# Sensor_ExpandBoard_LED.net
KiCad netlist of a schematic drawn in Altium Designer
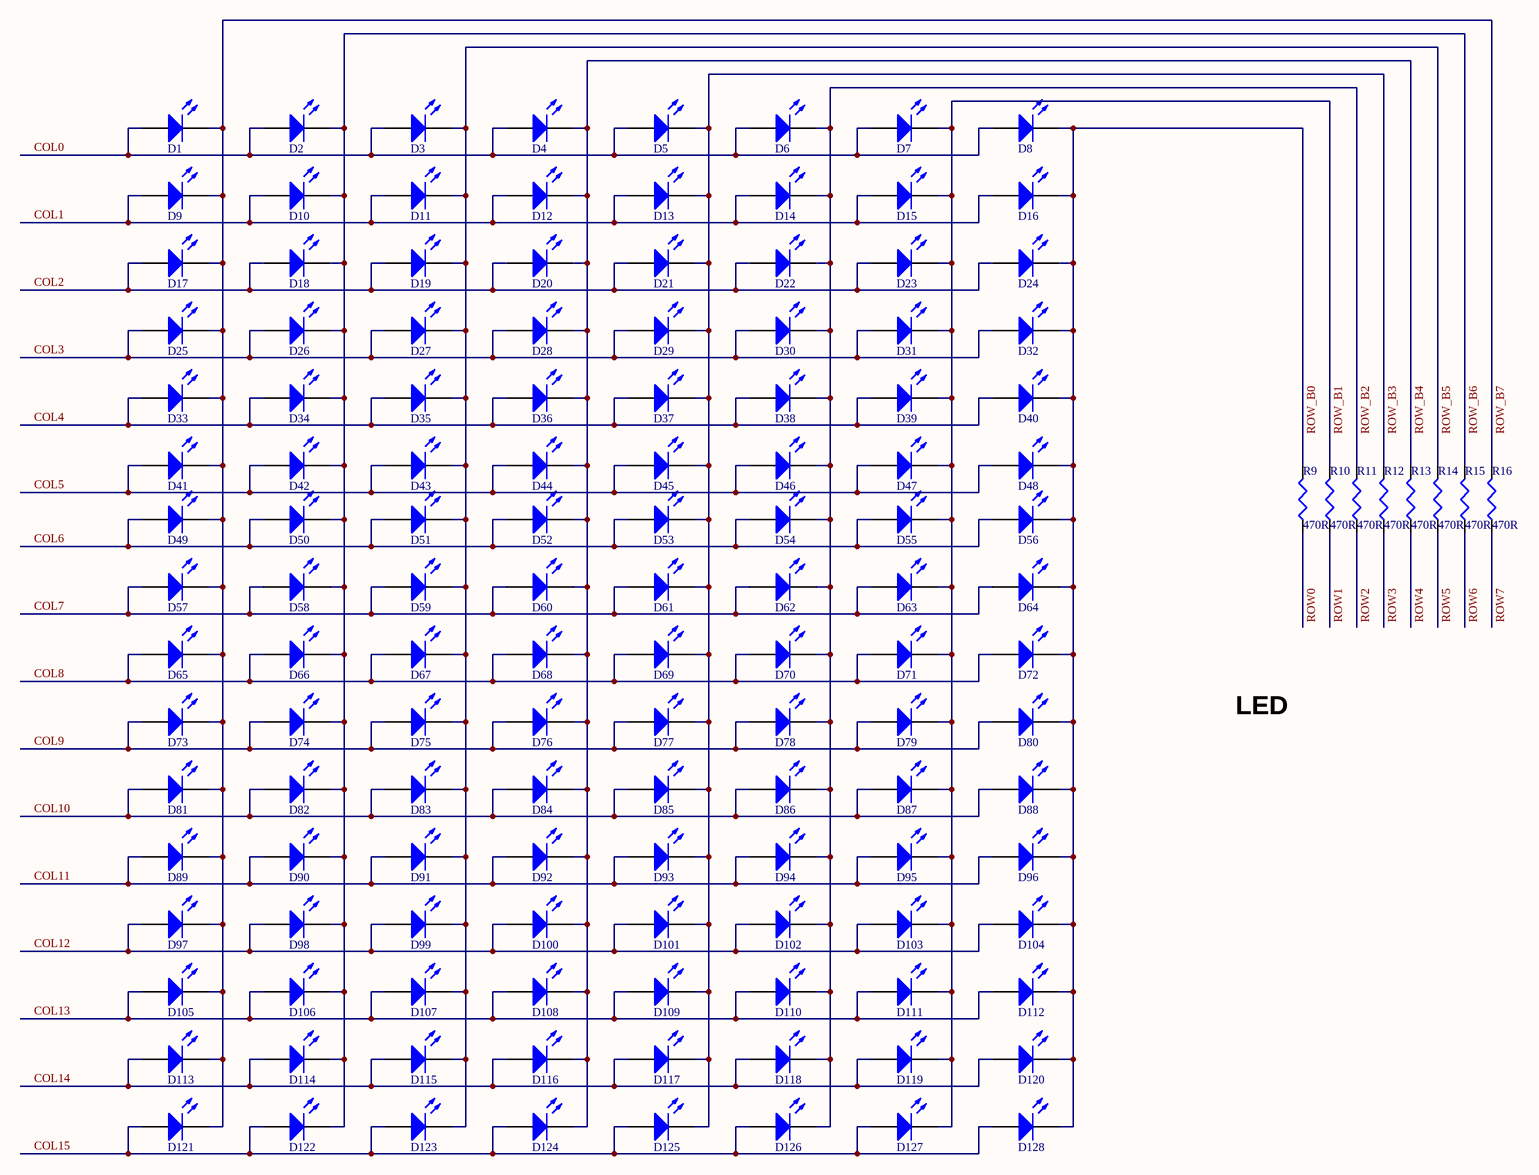
[diagram p0: Sensor_ExpandBoard_LED.SchDoc]

(export (version "E")
  (design (tool "Eeschema 10.0.6"))
  (components
    (comp (ref "D1")
      (value "Red")
      (footprint "LED_0603_SMALL")
      (description "发光二极管")
      (fields (field (name "PUBLISHER") "Altium Limited"))
      (libsource (lib "step") (part "LED"))
    )
    (comp (ref "D2")
      (value "Red")
      (footprint "LED_0603_SMALL")
      (description "发光二极管")
      (fields (field (name "PUBLISHER") "Altium Limited"))
      (libsource (lib "step") (part "LED"))
    )
    (comp (ref "D3")
      (value "Red")
      (footprint "LED_0603_SMALL")
      (description "发光二极管")
      (fields (field (name "PUBLISHER") "Altium Limited"))
      (libsource (lib "step") (part "LED"))
    )
    (comp (ref "D4")
      (value "Red")
      (footprint "LED_0603_SMALL")
      (description "发光二极管")
      (fields (field (name "PUBLISHER") "Altium Limited"))
      (libsource (lib "step") (part "LED"))
    )
    (comp (ref "D5")
      (value "Red")
      (footprint "LED_0603_SMALL")
      (description "发光二极管")
      (fields (field (name "PUBLISHER") "Altium Limited"))
      (libsource (lib "step") (part "LED"))
    )
    (comp (ref "D6")
      (value "Red")
      (footprint "LED_0603_SMALL")
      (description "发光二极管")
      (fields (field (name "PUBLISHER") "Altium Limited"))
      (libsource (lib "step") (part "LED"))
    )
    (comp (ref "D7")
      (value "Red")
      (footprint "LED_0603_SMALL")
      (description "发光二极管")
      (fields (field (name "PUBLISHER") "Altium Limited"))
      (libsource (lib "step") (part "LED"))
    )
    (comp (ref "D8")
      (value "Red")
      (footprint "LED_0603_SMALL")
      (description "发光二极管")
      (fields (field (name "PUBLISHER") "Altium Limited"))
      (libsource (lib "step") (part "LED"))
    )
    (comp (ref "D9")
      (value "Red")
      (footprint "LED_0603_SMALL")
      (description "发光二极管")
      (fields (field (name "PUBLISHER") "Altium Limited"))
      (libsource (lib "step") (part "LED"))
    )
    (comp (ref "D10")
      (value "Red")
      (footprint "LED_0603_SMALL")
      (description "发光二极管")
      (fields (field (name "PUBLISHER") "Altium Limited"))
      (libsource (lib "step") (part "LED"))
    )
    (comp (ref "D11")
      (value "Red")
      (footprint "LED_0603_SMALL")
      (description "发光二极管")
      (fields (field (name "PUBLISHER") "Altium Limited"))
      (libsource (lib "step") (part "LED"))
    )
    (comp (ref "D12")
      (value "Red")
      (footprint "LED_0603_SMALL")
      (description "发光二极管")
      (fields (field (name "PUBLISHER") "Altium Limited"))
      (libsource (lib "step") (part "LED"))
    )
    (comp (ref "D13")
      (value "Red")
      (footprint "LED_0603_SMALL")
      (description "发光二极管")
      (fields (field (name "PUBLISHER") "Altium Limited"))
      (libsource (lib "step") (part "LED"))
    )
    (comp (ref "D14")
      (value "Red")
      (footprint "LED_0603_SMALL")
      (description "发光二极管")
      (fields (field (name "PUBLISHER") "Altium Limited"))
      (libsource (lib "step") (part "LED"))
    )
    (comp (ref "D15")
      (value "Red")
      (footprint "LED_0603_SMALL")
      (description "发光二极管")
      (fields (field (name "PUBLISHER") "Altium Limited"))
      (libsource (lib "step") (part "LED"))
    )
    (comp (ref "D16")
      (value "Red")
      (footprint "LED_0603_SMALL")
      (description "发光二极管")
      (fields (field (name "PUBLISHER") "Altium Limited"))
      (libsource (lib "step") (part "LED"))
    )
    (comp (ref "D17")
      (value "Red")
      (footprint "LED_0603_SMALL")
      (description "发光二极管")
      (fields (field (name "PUBLISHER") "Altium Limited"))
      (libsource (lib "step") (part "LED"))
    )
    (comp (ref "D18")
      (value "Red")
      (footprint "LED_0603_SMALL")
      (description "发光二极管")
      (fields (field (name "PUBLISHER") "Altium Limited"))
      (libsource (lib "step") (part "LED"))
    )
    (comp (ref "D19")
      (value "Red")
      (footprint "LED_0603_SMALL")
      (description "发光二极管")
      (fields (field (name "PUBLISHER") "Altium Limited"))
      (libsource (lib "step") (part "LED"))
    )
    (comp (ref "D20")
      (value "Red")
      (footprint "LED_0603_SMALL")
      (description "发光二极管")
      (fields (field (name "PUBLISHER") "Altium Limited"))
      (libsource (lib "step") (part "LED"))
    )
    (comp (ref "D21")
      (value "Red")
      (footprint "LED_0603_SMALL")
      (description "发光二极管")
      (fields (field (name "PUBLISHER") "Altium Limited"))
      (libsource (lib "step") (part "LED"))
    )
    (comp (ref "D22")
      (value "Red")
      (footprint "LED_0603_SMALL")
      (description "发光二极管")
      (fields (field (name "PUBLISHER") "Altium Limited"))
      (libsource (lib "step") (part "LED"))
    )
    (comp (ref "D23")
      (value "Red")
      (footprint "LED_0603_SMALL")
      (description "发光二极管")
      (fields (field (name "PUBLISHER") "Altium Limited"))
      (libsource (lib "step") (part "LED"))
    )
    (comp (ref "D24")
      (value "Red")
      (footprint "LED_0603_SMALL")
      (description "发光二极管")
      (fields (field (name "PUBLISHER") "Altium Limited"))
      (libsource (lib "step") (part "LED"))
    )
    (comp (ref "D25")
      (value "Red")
      (footprint "LED_0603_SMALL")
      (description "发光二极管")
      (fields (field (name "PUBLISHER") "Altium Limited"))
      (libsource (lib "step") (part "LED"))
    )
    (comp (ref "D26")
      (value "Red")
      (footprint "LED_0603_SMALL")
      (description "发光二极管")
      (fields (field (name "PUBLISHER") "Altium Limited"))
      (libsource (lib "step") (part "LED"))
    )
    (comp (ref "D27")
      (value "Red")
      (footprint "LED_0603_SMALL")
      (description "发光二极管")
      (fields (field (name "PUBLISHER") "Altium Limited"))
      (libsource (lib "step") (part "LED"))
    )
    (comp (ref "D28")
      (value "Red")
      (footprint "LED_0603_SMALL")
      (description "发光二极管")
      (fields (field (name "PUBLISHER") "Altium Limited"))
      (libsource (lib "step") (part "LED"))
    )
    (comp (ref "D29")
      (value "Red")
      (footprint "LED_0603_SMALL")
      (description "发光二极管")
      (fields (field (name "PUBLISHER") "Altium Limited"))
      (libsource (lib "step") (part "LED"))
    )
    (comp (ref "D30")
      (value "Red")
      (footprint "LED_0603_SMALL")
      (description "发光二极管")
      (fields (field (name "PUBLISHER") "Altium Limited"))
      (libsource (lib "step") (part "LED"))
    )
    (comp (ref "D31")
      (value "Red")
      (footprint "LED_0603_SMALL")
      (description "发光二极管")
      (fields (field (name "PUBLISHER") "Altium Limited"))
      (libsource (lib "step") (part "LED"))
    )
    (comp (ref "D32")
      (value "Red")
      (footprint "LED_0603_SMALL")
      (description "发光二极管")
      (fields (field (name "PUBLISHER") "Altium Limited"))
      (libsource (lib "step") (part "LED"))
    )
    (comp (ref "D33")
      (value "Red")
      (footprint "LED_0603_SMALL")
      (description "发光二极管")
      (fields (field (name "PUBLISHER") "Altium Limited"))
      (libsource (lib "step") (part "LED"))
    )
    (comp (ref "D34")
      (value "Red")
      (footprint "LED_0603_SMALL")
      (description "发光二极管")
      (fields (field (name "PUBLISHER") "Altium Limited"))
      (libsource (lib "step") (part "LED"))
    )
    (comp (ref "D35")
      (value "Red")
      (footprint "LED_0603_SMALL")
      (description "发光二极管")
      (fields (field (name "PUBLISHER") "Altium Limited"))
      (libsource (lib "step") (part "LED"))
    )
    (comp (ref "D36")
      (value "Red")
      (footprint "LED_0603_SMALL")
      (description "发光二极管")
      (fields (field (name "PUBLISHER") "Altium Limited"))
      (libsource (lib "step") (part "LED"))
    )
    (comp (ref "D37")
      (value "Red")
      (footprint "LED_0603_SMALL")
      (description "发光二极管")
      (fields (field (name "PUBLISHER") "Altium Limited"))
      (libsource (lib "step") (part "LED"))
    )
    (comp (ref "D38")
      (value "Red")
      (footprint "LED_0603_SMALL")
      (description "发光二极管")
      (fields (field (name "PUBLISHER") "Altium Limited"))
      (libsource (lib "step") (part "LED"))
    )
    (comp (ref "D39")
      (value "Red")
      (footprint "LED_0603_SMALL")
      (description "发光二极管")
      (fields (field (name "PUBLISHER") "Altium Limited"))
      (libsource (lib "step") (part "LED"))
    )
    (comp (ref "D40")
      (value "Red")
      (footprint "LED_0603_SMALL")
      (description "发光二极管")
      (fields (field (name "PUBLISHER") "Altium Limited"))
      (libsource (lib "step") (part "LED"))
    )
    (comp (ref "D41")
      (value "Red")
      (footprint "LED_0603_SMALL")
      (description "发光二极管")
      (fields (field (name "PUBLISHER") "Altium Limited"))
      (libsource (lib "step") (part "LED"))
    )
    (comp (ref "D42")
      (value "Red")
      (footprint "LED_0603_SMALL")
      (description "发光二极管")
      (fields (field (name "PUBLISHER") "Altium Limited"))
      (libsource (lib "step") (part "LED"))
    )
    (comp (ref "D43")
      (value "Red")
      (footprint "LED_0603_SMALL")
      (description "发光二极管")
      (fields (field (name "PUBLISHER") "Altium Limited"))
      (libsource (lib "step") (part "LED"))
    )
    (comp (ref "D44")
      (value "Red")
      (footprint "LED_0603_SMALL")
      (description "发光二极管")
      (fields (field (name "PUBLISHER") "Altium Limited"))
      (libsource (lib "step") (part "LED"))
    )
    (comp (ref "D45")
      (value "Red")
      (footprint "LED_0603_SMALL")
      (description "发光二极管")
      (fields (field (name "PUBLISHER") "Altium Limited"))
      (libsource (lib "step") (part "LED"))
    )
    (comp (ref "D46")
      (value "Red")
      (footprint "LED_0603_SMALL")
      (description "发光二极管")
      (fields (field (name "PUBLISHER") "Altium Limited"))
      (libsource (lib "step") (part "LED"))
    )
    (comp (ref "D47")
      (value "Red")
      (footprint "LED_0603_SMALL")
      (description "发光二极管")
      (fields (field (name "PUBLISHER") "Altium Limited"))
      (libsource (lib "step") (part "LED"))
    )
    (comp (ref "D48")
      (value "Red")
      (footprint "LED_0603_SMALL")
      (description "发光二极管")
      (fields (field (name "PUBLISHER") "Altium Limited"))
      (libsource (lib "step") (part "LED"))
    )
    (comp (ref "D49")
      (value "Red")
      (footprint "LED_0603_SMALL")
      (description "发光二极管")
      (fields (field (name "PUBLISHER") "Altium Limited"))
      (libsource (lib "step") (part "LED"))
    )
    (comp (ref "D50")
      (value "Red")
      (footprint "LED_0603_SMALL")
      (description "发光二极管")
      (fields (field (name "PUBLISHER") "Altium Limited"))
      (libsource (lib "step") (part "LED"))
    )
    (comp (ref "D51")
      (value "Red")
      (footprint "LED_0603_SMALL")
      (description "发光二极管")
      (fields (field (name "PUBLISHER") "Altium Limited"))
      (libsource (lib "step") (part "LED"))
    )
    (comp (ref "D52")
      (value "Red")
      (footprint "LED_0603_SMALL")
      (description "发光二极管")
      (fields (field (name "PUBLISHER") "Altium Limited"))
      (libsource (lib "step") (part "LED"))
    )
    (comp (ref "D53")
      (value "Red")
      (footprint "LED_0603_SMALL")
      (description "发光二极管")
      (fields (field (name "PUBLISHER") "Altium Limited"))
      (libsource (lib "step") (part "LED"))
    )
    (comp (ref "D54")
      (value "Red")
      (footprint "LED_0603_SMALL")
      (description "发光二极管")
      (fields (field (name "PUBLISHER") "Altium Limited"))
      (libsource (lib "step") (part "LED"))
    )
    (comp (ref "D55")
      (value "Red")
      (footprint "LED_0603_SMALL")
      (description "发光二极管")
      (fields (field (name "PUBLISHER") "Altium Limited"))
      (libsource (lib "step") (part "LED"))
    )
    (comp (ref "D56")
      (value "Red")
      (footprint "LED_0603_SMALL")
      (description "发光二极管")
      (fields (field (name "PUBLISHER") "Altium Limited"))
      (libsource (lib "step") (part "LED"))
    )
    (comp (ref "D57")
      (value "Red")
      (footprint "LED_0603_SMALL")
      (description "发光二极管")
      (fields (field (name "PUBLISHER") "Altium Limited"))
      (libsource (lib "step") (part "LED"))
    )
    (comp (ref "D58")
      (value "Red")
      (footprint "LED_0603_SMALL")
      (description "发光二极管")
      (fields (field (name "PUBLISHER") "Altium Limited"))
      (libsource (lib "step") (part "LED"))
    )
    (comp (ref "D59")
      (value "Red")
      (footprint "LED_0603_SMALL")
      (description "发光二极管")
      (fields (field (name "PUBLISHER") "Altium Limited"))
      (libsource (lib "step") (part "LED"))
    )
    (comp (ref "D60")
      (value "Red")
      (footprint "LED_0603_SMALL")
      (description "发光二极管")
      (fields (field (name "PUBLISHER") "Altium Limited"))
      (libsource (lib "step") (part "LED"))
    )
    (comp (ref "D61")
      (value "Red")
      (footprint "LED_0603_SMALL")
      (description "发光二极管")
      (fields (field (name "PUBLISHER") "Altium Limited"))
      (libsource (lib "step") (part "LED"))
    )
    (comp (ref "D62")
      (value "Red")
      (footprint "LED_0603_SMALL")
      (description "发光二极管")
      (fields (field (name "PUBLISHER") "Altium Limited"))
      (libsource (lib "step") (part "LED"))
    )
    (comp (ref "D63")
      (value "Red")
      (footprint "LED_0603_SMALL")
      (description "发光二极管")
      (fields (field (name "PUBLISHER") "Altium Limited"))
      (libsource (lib "step") (part "LED"))
    )
    (comp (ref "D64")
      (value "Red")
      (footprint "LED_0603_SMALL")
      (description "发光二极管")
      (fields (field (name "PUBLISHER") "Altium Limited"))
      (libsource (lib "step") (part "LED"))
    )
    (comp (ref "D65")
      (value "Red")
      (footprint "LED_0603_SMALL")
      (description "发光二极管")
      (fields (field (name "PUBLISHER") "Altium Limited"))
      (libsource (lib "step") (part "LED"))
    )
    (comp (ref "D66")
      (value "Red")
      (footprint "LED_0603_SMALL")
      (description "发光二极管")
      (fields (field (name "PUBLISHER") "Altium Limited"))
      (libsource (lib "step") (part "LED"))
    )
    (comp (ref "D67")
      (value "Red")
      (footprint "LED_0603_SMALL")
      (description "发光二极管")
      (fields (field (name "PUBLISHER") "Altium Limited"))
      (libsource (lib "step") (part "LED"))
    )
    (comp (ref "D68")
      (value "Red")
      (footprint "LED_0603_SMALL")
      (description "发光二极管")
      (fields (field (name "PUBLISHER") "Altium Limited"))
      (libsource (lib "step") (part "LED"))
    )
    (comp (ref "D69")
      (value "Red")
      (footprint "LED_0603_SMALL")
      (description "发光二极管")
      (fields (field (name "PUBLISHER") "Altium Limited"))
      (libsource (lib "step") (part "LED"))
    )
    (comp (ref "D70")
      (value "Red")
      (footprint "LED_0603_SMALL")
      (description "发光二极管")
      (fields (field (name "PUBLISHER") "Altium Limited"))
      (libsource (lib "step") (part "LED"))
    )
    (comp (ref "D71")
      (value "Red")
      (footprint "LED_0603_SMALL")
      (description "发光二极管")
      (fields (field (name "PUBLISHER") "Altium Limited"))
      (libsource (lib "step") (part "LED"))
    )
    (comp (ref "D72")
      (value "Red")
      (footprint "LED_0603_SMALL")
      (description "发光二极管")
      (fields (field (name "PUBLISHER") "Altium Limited"))
      (libsource (lib "step") (part "LED"))
    )
    (comp (ref "D73")
      (value "Red")
      (footprint "LED_0603_SMALL")
      (description "发光二极管")
      (fields (field (name "PUBLISHER") "Altium Limited"))
      (libsource (lib "step") (part "LED"))
    )
    (comp (ref "D74")
      (value "Red")
      (footprint "LED_0603_SMALL")
      (description "发光二极管")
      (fields (field (name "PUBLISHER") "Altium Limited"))
      (libsource (lib "step") (part "LED"))
    )
    (comp (ref "D75")
      (value "Red")
      (footprint "LED_0603_SMALL")
      (description "发光二极管")
      (fields (field (name "PUBLISHER") "Altium Limited"))
      (libsource (lib "step") (part "LED"))
    )
    (comp (ref "D76")
      (value "Red")
      (footprint "LED_0603_SMALL")
      (description "发光二极管")
      (fields (field (name "PUBLISHER") "Altium Limited"))
      (libsource (lib "step") (part "LED"))
    )
    (comp (ref "D77")
      (value "Red")
      (footprint "LED_0603_SMALL")
      (description "发光二极管")
      (fields (field (name "PUBLISHER") "Altium Limited"))
      (libsource (lib "step") (part "LED"))
    )
    (comp (ref "D78")
      (value "Red")
      (footprint "LED_0603_SMALL")
      (description "发光二极管")
      (fields (field (name "PUBLISHER") "Altium Limited"))
      (libsource (lib "step") (part "LED"))
    )
    (comp (ref "D79")
      (value "Red")
      (footprint "LED_0603_SMALL")
      (description "发光二极管")
      (fields (field (name "PUBLISHER") "Altium Limited"))
      (libsource (lib "step") (part "LED"))
    )
    (comp (ref "D80")
      (value "Red")
      (footprint "LED_0603_SMALL")
      (description "发光二极管")
      (fields (field (name "PUBLISHER") "Altium Limited"))
      (libsource (lib "step") (part "LED"))
    )
    (comp (ref "D81")
      (value "Red")
      (footprint "LED_0603_SMALL")
      (description "发光二极管")
      (fields (field (name "PUBLISHER") "Altium Limited"))
      (libsource (lib "step") (part "LED"))
    )
    (comp (ref "D82")
      (value "Red")
      (footprint "LED_0603_SMALL")
      (description "发光二极管")
      (fields (field (name "PUBLISHER") "Altium Limited"))
      (libsource (lib "step") (part "LED"))
    )
    (comp (ref "D83")
      (value "Red")
      (footprint "LED_0603_SMALL")
      (description "发光二极管")
      (fields (field (name "PUBLISHER") "Altium Limited"))
      (libsource (lib "step") (part "LED"))
    )
    (comp (ref "D84")
      (value "Red")
      (footprint "LED_0603_SMALL")
      (description "发光二极管")
      (fields (field (name "PUBLISHER") "Altium Limited"))
      (libsource (lib "step") (part "LED"))
    )
    (comp (ref "D85")
      (value "Red")
      (footprint "LED_0603_SMALL")
      (description "发光二极管")
      (fields (field (name "PUBLISHER") "Altium Limited"))
      (libsource (lib "step") (part "LED"))
    )
    (comp (ref "D86")
      (value "Red")
      (footprint "LED_0603_SMALL")
      (description "发光二极管")
      (fields (field (name "PUBLISHER") "Altium Limited"))
      (libsource (lib "step") (part "LED"))
    )
    (comp (ref "D87")
      (value "Red")
      (footprint "LED_0603_SMALL")
      (description "发光二极管")
      (fields (field (name "PUBLISHER") "Altium Limited"))
      (libsource (lib "step") (part "LED"))
    )
    (comp (ref "D88")
      (value "Red")
      (footprint "LED_0603_SMALL")
      (description "发光二极管")
      (fields (field (name "PUBLISHER") "Altium Limited"))
      (libsource (lib "step") (part "LED"))
    )
    (comp (ref "D89")
      (value "Red")
      (footprint "LED_0603_SMALL")
      (description "发光二极管")
      (fields (field (name "PUBLISHER") "Altium Limited"))
      (libsource (lib "step") (part "LED"))
    )
    (comp (ref "D90")
      (value "Red")
      (footprint "LED_0603_SMALL")
      (description "发光二极管")
      (fields (field (name "PUBLISHER") "Altium Limited"))
      (libsource (lib "step") (part "LED"))
    )
    (comp (ref "D91")
      (value "Red")
      (footprint "LED_0603_SMALL")
      (description "发光二极管")
      (fields (field (name "PUBLISHER") "Altium Limited"))
      (libsource (lib "step") (part "LED"))
    )
    (comp (ref "D92")
      (value "Red")
      (footprint "LED_0603_SMALL")
      (description "发光二极管")
      (fields (field (name "PUBLISHER") "Altium Limited"))
      (libsource (lib "step") (part "LED"))
    )
    (comp (ref "D93")
      (value "Red")
      (footprint "LED_0603_SMALL")
      (description "发光二极管")
      (fields (field (name "PUBLISHER") "Altium Limited"))
      (libsource (lib "step") (part "LED"))
    )
    (comp (ref "D94")
      (value "Red")
      (footprint "LED_0603_SMALL")
      (description "发光二极管")
      (fields (field (name "PUBLISHER") "Altium Limited"))
      (libsource (lib "step") (part "LED"))
    )
    (comp (ref "D95")
      (value "Red")
      (footprint "LED_0603_SMALL")
      (description "发光二极管")
      (fields (field (name "PUBLISHER") "Altium Limited"))
      (libsource (lib "step") (part "LED"))
    )
    (comp (ref "D96")
      (value "Red")
      (footprint "LED_0603_SMALL")
      (description "发光二极管")
      (fields (field (name "PUBLISHER") "Altium Limited"))
      (libsource (lib "step") (part "LED"))
    )
    (comp (ref "D97")
      (value "Red")
      (footprint "LED_0603_SMALL")
      (description "发光二极管")
      (fields (field (name "PUBLISHER") "Altium Limited"))
      (libsource (lib "step") (part "LED"))
    )
    (comp (ref "D98")
      (value "Red")
      (footprint "LED_0603_SMALL")
      (description "发光二极管")
      (fields (field (name "PUBLISHER") "Altium Limited"))
      (libsource (lib "step") (part "LED"))
    )
    (comp (ref "D99")
      (value "Red")
      (footprint "LED_0603_SMALL")
      (description "发光二极管")
      (fields (field (name "PUBLISHER") "Altium Limited"))
      (libsource (lib "step") (part "LED"))
    )
    (comp (ref "D100")
      (value "Red")
      (footprint "LED_0603_SMALL")
      (description "发光二极管")
      (fields (field (name "PUBLISHER") "Altium Limited"))
      (libsource (lib "step") (part "LED"))
    )
    (comp (ref "D101")
      (value "Red")
      (footprint "LED_0603_SMALL")
      (description "发光二极管")
      (fields (field (name "PUBLISHER") "Altium Limited"))
      (libsource (lib "step") (part "LED"))
    )
    (comp (ref "D102")
      (value "Red")
      (footprint "LED_0603_SMALL")
      (description "发光二极管")
      (fields (field (name "PUBLISHER") "Altium Limited"))
      (libsource (lib "step") (part "LED"))
    )
    (comp (ref "D103")
      (value "Red")
      (footprint "LED_0603_SMALL")
      (description "发光二极管")
      (fields (field (name "PUBLISHER") "Altium Limited"))
      (libsource (lib "step") (part "LED"))
    )
    (comp (ref "D104")
      (value "Red")
      (footprint "LED_0603_SMALL")
      (description "发光二极管")
      (fields (field (name "PUBLISHER") "Altium Limited"))
      (libsource (lib "step") (part "LED"))
    )
    (comp (ref "D105")
      (value "Red")
      (footprint "LED_0603_SMALL")
      (description "发光二极管")
      (fields (field (name "PUBLISHER") "Altium Limited"))
      (libsource (lib "step") (part "LED"))
    )
    (comp (ref "D106")
      (value "Red")
      (footprint "LED_0603_SMALL")
      (description "发光二极管")
      (fields (field (name "PUBLISHER") "Altium Limited"))
      (libsource (lib "step") (part "LED"))
    )
    (comp (ref "D107")
      (value "Red")
      (footprint "LED_0603_SMALL")
      (description "发光二极管")
      (fields (field (name "PUBLISHER") "Altium Limited"))
      (libsource (lib "step") (part "LED"))
    )
    (comp (ref "D108")
      (value "Red")
      (footprint "LED_0603_SMALL")
      (description "发光二极管")
      (fields (field (name "PUBLISHER") "Altium Limited"))
      (libsource (lib "step") (part "LED"))
    )
    (comp (ref "D109")
      (value "Red")
      (footprint "LED_0603_SMALL")
      (description "发光二极管")
      (fields (field (name "PUBLISHER") "Altium Limited"))
      (libsource (lib "step") (part "LED"))
    )
    (comp (ref "D110")
      (value "Red")
      (footprint "LED_0603_SMALL")
      (description "发光二极管")
      (fields (field (name "PUBLISHER") "Altium Limited"))
      (libsource (lib "step") (part "LED"))
    )
    (comp (ref "D111")
      (value "Red")
      (footprint "LED_0603_SMALL")
      (description "发光二极管")
      (fields (field (name "PUBLISHER") "Altium Limited"))
      (libsource (lib "step") (part "LED"))
    )
    (comp (ref "D112")
      (value "Red")
      (footprint "LED_0603_SMALL")
      (description "发光二极管")
      (fields (field (name "PUBLISHER") "Altium Limited"))
      (libsource (lib "step") (part "LED"))
    )
    (comp (ref "D113")
      (value "Red")
      (footprint "LED_0603_SMALL")
      (description "发光二极管")
      (fields (field (name "PUBLISHER") "Altium Limited"))
      (libsource (lib "step") (part "LED"))
    )
    (comp (ref "D114")
      (value "Red")
      (footprint "LED_0603_SMALL")
      (description "发光二极管")
      (fields (field (name "PUBLISHER") "Altium Limited"))
      (libsource (lib "step") (part "LED"))
    )
    (comp (ref "D115")
      (value "Red")
      (footprint "LED_0603_SMALL")
      (description "发光二极管")
      (fields (field (name "PUBLISHER") "Altium Limited"))
      (libsource (lib "step") (part "LED"))
    )
    (comp (ref "D116")
      (value "Red")
      (footprint "LED_0603_SMALL")
      (description "发光二极管")
      (fields (field (name "PUBLISHER") "Altium Limited"))
      (libsource (lib "step") (part "LED"))
    )
    (comp (ref "D117")
      (value "Red")
      (footprint "LED_0603_SMALL")
      (description "发光二极管")
      (fields (field (name "PUBLISHER") "Altium Limited"))
      (libsource (lib "step") (part "LED"))
    )
    (comp (ref "D118")
      (value "Red")
      (footprint "LED_0603_SMALL")
      (description "发光二极管")
      (fields (field (name "PUBLISHER") "Altium Limited"))
      (libsource (lib "step") (part "LED"))
    )
    (comp (ref "D119")
      (value "Red")
      (footprint "LED_0603_SMALL")
      (description "发光二极管")
      (fields (field (name "PUBLISHER") "Altium Limited"))
      (libsource (lib "step") (part "LED"))
    )
    (comp (ref "D120")
      (value "Red")
      (footprint "LED_0603_SMALL")
      (description "发光二极管")
      (fields (field (name "PUBLISHER") "Altium Limited"))
      (libsource (lib "step") (part "LED"))
    )
    (comp (ref "D121")
      (value "Red")
      (footprint "LED_0603_SMALL")
      (description "发光二极管")
      (fields (field (name "PUBLISHER") "Altium Limited"))
      (libsource (lib "step") (part "LED"))
    )
    (comp (ref "D122")
      (value "Red")
      (footprint "LED_0603_SMALL")
      (description "发光二极管")
      (fields (field (name "PUBLISHER") "Altium Limited"))
      (libsource (lib "step") (part "LED"))
    )
    (comp (ref "D123")
      (value "Red")
      (footprint "LED_0603_SMALL")
      (description "发光二极管")
      (fields (field (name "PUBLISHER") "Altium Limited"))
      (libsource (lib "step") (part "LED"))
    )
    (comp (ref "D124")
      (value "Red")
      (footprint "LED_0603_SMALL")
      (description "发光二极管")
      (fields (field (name "PUBLISHER") "Altium Limited"))
      (libsource (lib "step") (part "LED"))
    )
    (comp (ref "D125")
      (value "Red")
      (footprint "LED_0603_SMALL")
      (description "发光二极管")
      (fields (field (name "PUBLISHER") "Altium Limited"))
      (libsource (lib "step") (part "LED"))
    )
    (comp (ref "D126")
      (value "Red")
      (footprint "LED_0603_SMALL")
      (description "发光二极管")
      (fields (field (name "PUBLISHER") "Altium Limited"))
      (libsource (lib "step") (part "LED"))
    )
    (comp (ref "D127")
      (value "Red")
      (footprint "LED_0603_SMALL")
      (description "发光二极管")
      (fields (field (name "PUBLISHER") "Altium Limited"))
      (libsource (lib "step") (part "LED"))
    )
    (comp (ref "D128")
      (value "Red")
      (footprint "LED_0603_SMALL")
      (description "发光二极管")
      (fields (field (name "PUBLISHER") "Altium Limited"))
      (libsource (lib "step") (part "LED"))
    )
    (comp (ref "R9")
      (value "470R")
      (footprint "R0603")
      (description "Resistor")
      (fields (field (name "PUBLISHER") "Altium Limited"))
      (libsource (lib "step") (part "Res"))
    )
    (comp (ref "R10")
      (value "470R")
      (footprint "R0603")
      (description "Resistor")
      (fields (field (name "PUBLISHER") "Altium Limited"))
      (libsource (lib "step") (part "Res"))
    )
    (comp (ref "R11")
      (value "470R")
      (footprint "R0603")
      (description "Resistor")
      (fields (field (name "PUBLISHER") "Altium Limited"))
      (libsource (lib "step") (part "Res"))
    )
    (comp (ref "R12")
      (value "470R")
      (footprint "R0603")
      (description "Resistor")
      (fields (field (name "PUBLISHER") "Altium Limited"))
      (libsource (lib "step") (part "Res"))
    )
    (comp (ref "R13")
      (value "470R")
      (footprint "R0603")
      (description "Resistor")
      (fields (field (name "PUBLISHER") "Altium Limited"))
      (libsource (lib "step") (part "Res"))
    )
    (comp (ref "R14")
      (value "470R")
      (footprint "R0603")
      (description "Resistor")
      (fields (field (name "PUBLISHER") "Altium Limited"))
      (libsource (lib "step") (part "Res"))
    )
    (comp (ref "R15")
      (value "470R")
      (footprint "R0603")
      (description "Resistor")
      (fields (field (name "PUBLISHER") "Altium Limited"))
      (libsource (lib "step") (part "Res"))
    )
    (comp (ref "R16")
      (value "470R")
      (footprint "R0603")
      (description "Resistor")
      (fields (field (name "PUBLISHER") "Altium Limited"))
      (libsource (lib "step") (part "Res"))
    )
  )
  (nets
    (net (code "1") (name "/COL0") (class "Default")
      (node (ref "D1") (pin "1") (pinfunction "A_1") (pintype "passive"))
      (node (ref "D2") (pin "1") (pinfunction "A_1") (pintype "passive"))
      (node (ref "D3") (pin "1") (pinfunction "A_1") (pintype "passive"))
      (node (ref "D4") (pin "1") (pinfunction "A_1") (pintype "passive"))
      (node (ref "D5") (pin "1") (pinfunction "A_1") (pintype "passive"))
      (node (ref "D6") (pin "1") (pinfunction "A_1") (pintype "passive"))
      (node (ref "D7") (pin "1") (pinfunction "A_1") (pintype "passive"))
      (node (ref "D8") (pin "1") (pinfunction "A_1") (pintype "passive"))
    )
    (net (code "2") (name "/COL1") (class "Default")
      (node (ref "D10") (pin "1") (pinfunction "A_1") (pintype "passive"))
      (node (ref "D11") (pin "1") (pinfunction "A_1") (pintype "passive"))
      (node (ref "D12") (pin "1") (pinfunction "A_1") (pintype "passive"))
      (node (ref "D13") (pin "1") (pinfunction "A_1") (pintype "passive"))
      (node (ref "D14") (pin "1") (pinfunction "A_1") (pintype "passive"))
      (node (ref "D15") (pin "1") (pinfunction "A_1") (pintype "passive"))
      (node (ref "D16") (pin "1") (pinfunction "A_1") (pintype "passive"))
      (node (ref "D9") (pin "1") (pinfunction "A_1") (pintype "passive"))
    )
    (net (code "3") (name "/COL2") (class "Default")
      (node (ref "D17") (pin "1") (pinfunction "A_1") (pintype "passive"))
      (node (ref "D18") (pin "1") (pinfunction "A_1") (pintype "passive"))
      (node (ref "D19") (pin "1") (pinfunction "A_1") (pintype "passive"))
      (node (ref "D20") (pin "1") (pinfunction "A_1") (pintype "passive"))
      (node (ref "D21") (pin "1") (pinfunction "A_1") (pintype "passive"))
      (node (ref "D22") (pin "1") (pinfunction "A_1") (pintype "passive"))
      (node (ref "D23") (pin "1") (pinfunction "A_1") (pintype "passive"))
      (node (ref "D24") (pin "1") (pinfunction "A_1") (pintype "passive"))
    )
    (net (code "4") (name "/COL3") (class "Default")
      (node (ref "D25") (pin "1") (pinfunction "A_1") (pintype "passive"))
      (node (ref "D26") (pin "1") (pinfunction "A_1") (pintype "passive"))
      (node (ref "D27") (pin "1") (pinfunction "A_1") (pintype "passive"))
      (node (ref "D28") (pin "1") (pinfunction "A_1") (pintype "passive"))
      (node (ref "D29") (pin "1") (pinfunction "A_1") (pintype "passive"))
      (node (ref "D30") (pin "1") (pinfunction "A_1") (pintype "passive"))
      (node (ref "D31") (pin "1") (pinfunction "A_1") (pintype "passive"))
      (node (ref "D32") (pin "1") (pinfunction "A_1") (pintype "passive"))
    )
    (net (code "5") (name "/COL4") (class "Default")
      (node (ref "D33") (pin "1") (pinfunction "A_1") (pintype "passive"))
      (node (ref "D34") (pin "1") (pinfunction "A_1") (pintype "passive"))
      (node (ref "D35") (pin "1") (pinfunction "A_1") (pintype "passive"))
      (node (ref "D36") (pin "1") (pinfunction "A_1") (pintype "passive"))
      (node (ref "D37") (pin "1") (pinfunction "A_1") (pintype "passive"))
      (node (ref "D38") (pin "1") (pinfunction "A_1") (pintype "passive"))
      (node (ref "D39") (pin "1") (pinfunction "A_1") (pintype "passive"))
      (node (ref "D40") (pin "1") (pinfunction "A_1") (pintype "passive"))
    )
    (net (code "6") (name "/COL5") (class "Default")
      (node (ref "D41") (pin "1") (pinfunction "A_1") (pintype "passive"))
      (node (ref "D42") (pin "1") (pinfunction "A_1") (pintype "passive"))
      (node (ref "D43") (pin "1") (pinfunction "A_1") (pintype "passive"))
      (node (ref "D44") (pin "1") (pinfunction "A_1") (pintype "passive"))
      (node (ref "D45") (pin "1") (pinfunction "A_1") (pintype "passive"))
      (node (ref "D46") (pin "1") (pinfunction "A_1") (pintype "passive"))
      (node (ref "D47") (pin "1") (pinfunction "A_1") (pintype "passive"))
      (node (ref "D48") (pin "1") (pinfunction "A_1") (pintype "passive"))
    )
    (net (code "7") (name "/COL6") (class "Default")
      (node (ref "D49") (pin "1") (pinfunction "A_1") (pintype "passive"))
      (node (ref "D50") (pin "1") (pinfunction "A_1") (pintype "passive"))
      (node (ref "D51") (pin "1") (pinfunction "A_1") (pintype "passive"))
      (node (ref "D52") (pin "1") (pinfunction "A_1") (pintype "passive"))
      (node (ref "D53") (pin "1") (pinfunction "A_1") (pintype "passive"))
      (node (ref "D54") (pin "1") (pinfunction "A_1") (pintype "passive"))
      (node (ref "D55") (pin "1") (pinfunction "A_1") (pintype "passive"))
      (node (ref "D56") (pin "1") (pinfunction "A_1") (pintype "passive"))
    )
    (net (code "8") (name "/COL7") (class "Default")
      (node (ref "D57") (pin "1") (pinfunction "A_1") (pintype "passive"))
      (node (ref "D58") (pin "1") (pinfunction "A_1") (pintype "passive"))
      (node (ref "D59") (pin "1") (pinfunction "A_1") (pintype "passive"))
      (node (ref "D60") (pin "1") (pinfunction "A_1") (pintype "passive"))
      (node (ref "D61") (pin "1") (pinfunction "A_1") (pintype "passive"))
      (node (ref "D62") (pin "1") (pinfunction "A_1") (pintype "passive"))
      (node (ref "D63") (pin "1") (pinfunction "A_1") (pintype "passive"))
      (node (ref "D64") (pin "1") (pinfunction "A_1") (pintype "passive"))
    )
    (net (code "9") (name "/COL8") (class "Default")
      (node (ref "D65") (pin "1") (pinfunction "A_1") (pintype "passive"))
      (node (ref "D66") (pin "1") (pinfunction "A_1") (pintype "passive"))
      (node (ref "D67") (pin "1") (pinfunction "A_1") (pintype "passive"))
      (node (ref "D68") (pin "1") (pinfunction "A_1") (pintype "passive"))
      (node (ref "D69") (pin "1") (pinfunction "A_1") (pintype "passive"))
      (node (ref "D70") (pin "1") (pinfunction "A_1") (pintype "passive"))
      (node (ref "D71") (pin "1") (pinfunction "A_1") (pintype "passive"))
      (node (ref "D72") (pin "1") (pinfunction "A_1") (pintype "passive"))
    )
    (net (code "10") (name "/COL9") (class "Default")
      (node (ref "D73") (pin "1") (pinfunction "A_1") (pintype "passive"))
      (node (ref "D74") (pin "1") (pinfunction "A_1") (pintype "passive"))
      (node (ref "D75") (pin "1") (pinfunction "A_1") (pintype "passive"))
      (node (ref "D76") (pin "1") (pinfunction "A_1") (pintype "passive"))
      (node (ref "D77") (pin "1") (pinfunction "A_1") (pintype "passive"))
      (node (ref "D78") (pin "1") (pinfunction "A_1") (pintype "passive"))
      (node (ref "D79") (pin "1") (pinfunction "A_1") (pintype "passive"))
      (node (ref "D80") (pin "1") (pinfunction "A_1") (pintype "passive"))
    )
    (net (code "11") (name "/COL10") (class "Default")
      (node (ref "D81") (pin "1") (pinfunction "A_1") (pintype "passive"))
      (node (ref "D82") (pin "1") (pinfunction "A_1") (pintype "passive"))
      (node (ref "D83") (pin "1") (pinfunction "A_1") (pintype "passive"))
      (node (ref "D84") (pin "1") (pinfunction "A_1") (pintype "passive"))
      (node (ref "D85") (pin "1") (pinfunction "A_1") (pintype "passive"))
      (node (ref "D86") (pin "1") (pinfunction "A_1") (pintype "passive"))
      (node (ref "D87") (pin "1") (pinfunction "A_1") (pintype "passive"))
      (node (ref "D88") (pin "1") (pinfunction "A_1") (pintype "passive"))
    )
    (net (code "12") (name "/COL11") (class "Default")
      (node (ref "D89") (pin "1") (pinfunction "A_1") (pintype "passive"))
      (node (ref "D90") (pin "1") (pinfunction "A_1") (pintype "passive"))
      (node (ref "D91") (pin "1") (pinfunction "A_1") (pintype "passive"))
      (node (ref "D92") (pin "1") (pinfunction "A_1") (pintype "passive"))
      (node (ref "D93") (pin "1") (pinfunction "A_1") (pintype "passive"))
      (node (ref "D94") (pin "1") (pinfunction "A_1") (pintype "passive"))
      (node (ref "D95") (pin "1") (pinfunction "A_1") (pintype "passive"))
      (node (ref "D96") (pin "1") (pinfunction "A_1") (pintype "passive"))
    )
    (net (code "13") (name "/COL12") (class "Default")
      (node (ref "D100") (pin "1") (pinfunction "A_1") (pintype "passive"))
      (node (ref "D101") (pin "1") (pinfunction "A_1") (pintype "passive"))
      (node (ref "D102") (pin "1") (pinfunction "A_1") (pintype "passive"))
      (node (ref "D103") (pin "1") (pinfunction "A_1") (pintype "passive"))
      (node (ref "D104") (pin "1") (pinfunction "A_1") (pintype "passive"))
      (node (ref "D97") (pin "1") (pinfunction "A_1") (pintype "passive"))
      (node (ref "D98") (pin "1") (pinfunction "A_1") (pintype "passive"))
      (node (ref "D99") (pin "1") (pinfunction "A_1") (pintype "passive"))
    )
    (net (code "14") (name "/COL13") (class "Default")
      (node (ref "D105") (pin "1") (pinfunction "A_1") (pintype "passive"))
      (node (ref "D106") (pin "1") (pinfunction "A_1") (pintype "passive"))
      (node (ref "D107") (pin "1") (pinfunction "A_1") (pintype "passive"))
      (node (ref "D108") (pin "1") (pinfunction "A_1") (pintype "passive"))
      (node (ref "D109") (pin "1") (pinfunction "A_1") (pintype "passive"))
      (node (ref "D110") (pin "1") (pinfunction "A_1") (pintype "passive"))
      (node (ref "D111") (pin "1") (pinfunction "A_1") (pintype "passive"))
      (node (ref "D112") (pin "1") (pinfunction "A_1") (pintype "passive"))
    )
    (net (code "15") (name "/COL14") (class "Default")
      (node (ref "D113") (pin "1") (pinfunction "A_1") (pintype "passive"))
      (node (ref "D114") (pin "1") (pinfunction "A_1") (pintype "passive"))
      (node (ref "D115") (pin "1") (pinfunction "A_1") (pintype "passive"))
      (node (ref "D116") (pin "1") (pinfunction "A_1") (pintype "passive"))
      (node (ref "D117") (pin "1") (pinfunction "A_1") (pintype "passive"))
      (node (ref "D118") (pin "1") (pinfunction "A_1") (pintype "passive"))
      (node (ref "D119") (pin "1") (pinfunction "A_1") (pintype "passive"))
      (node (ref "D120") (pin "1") (pinfunction "A_1") (pintype "passive"))
    )
    (net (code "16") (name "/COL15") (class "Default")
      (node (ref "D121") (pin "1") (pinfunction "A_1") (pintype "passive"))
      (node (ref "D122") (pin "1") (pinfunction "A_1") (pintype "passive"))
      (node (ref "D123") (pin "1") (pinfunction "A_1") (pintype "passive"))
      (node (ref "D124") (pin "1") (pinfunction "A_1") (pintype "passive"))
      (node (ref "D125") (pin "1") (pinfunction "A_1") (pintype "passive"))
      (node (ref "D126") (pin "1") (pinfunction "A_1") (pintype "passive"))
      (node (ref "D127") (pin "1") (pinfunction "A_1") (pintype "passive"))
      (node (ref "D128") (pin "1") (pinfunction "A_1") (pintype "passive"))
    )
    (net (code "17") (name "/ROW0") (class "Default")
      (node (ref "R9") (pin "1") (pinfunction "1_1") (pintype "passive"))
    )
    (net (code "18") (name "/ROW1") (class "Default")
      (node (ref "R10") (pin "1") (pinfunction "1_1") (pintype "passive"))
    )
    (net (code "19") (name "/ROW2") (class "Default")
      (node (ref "R11") (pin "1") (pinfunction "1_1") (pintype "passive"))
    )
    (net (code "20") (name "/ROW3") (class "Default")
      (node (ref "R12") (pin "1") (pinfunction "1_1") (pintype "passive"))
    )
    (net (code "21") (name "/ROW4") (class "Default")
      (node (ref "R13") (pin "1") (pinfunction "1_1") (pintype "passive"))
    )
    (net (code "22") (name "/ROW5") (class "Default")
      (node (ref "R14") (pin "1") (pinfunction "1_1") (pintype "passive"))
    )
    (net (code "23") (name "/ROW6") (class "Default")
      (node (ref "R15") (pin "1") (pinfunction "1_1") (pintype "passive"))
    )
    (net (code "24") (name "/ROW7") (class "Default")
      (node (ref "R16") (pin "1") (pinfunction "1_1") (pintype "passive"))
    )
    (net (code "25") (name "/ROW_B0") (class "Default")
      (node (ref "D104") (pin "2") (pinfunction "K_2") (pintype "passive"))
      (node (ref "D112") (pin "2") (pinfunction "K_2") (pintype "passive"))
      (node (ref "D120") (pin "2") (pinfunction "K_2") (pintype "passive"))
      (node (ref "D128") (pin "2") (pinfunction "K_2") (pintype "passive"))
      (node (ref "D16") (pin "2") (pinfunction "K_2") (pintype "passive"))
      (node (ref "D24") (pin "2") (pinfunction "K_2") (pintype "passive"))
      (node (ref "D32") (pin "2") (pinfunction "K_2") (pintype "passive"))
      (node (ref "D40") (pin "2") (pinfunction "K_2") (pintype "passive"))
      (node (ref "D48") (pin "2") (pinfunction "K_2") (pintype "passive"))
      (node (ref "D56") (pin "2") (pinfunction "K_2") (pintype "passive"))
      (node (ref "D64") (pin "2") (pinfunction "K_2") (pintype "passive"))
      (node (ref "D72") (pin "2") (pinfunction "K_2") (pintype "passive"))
      (node (ref "D8") (pin "2") (pinfunction "K_2") (pintype "passive"))
      (node (ref "D80") (pin "2") (pinfunction "K_2") (pintype "passive"))
      (node (ref "D88") (pin "2") (pinfunction "K_2") (pintype "passive"))
      (node (ref "D96") (pin "2") (pinfunction "K_2") (pintype "passive"))
      (node (ref "R9") (pin "2") (pinfunction "2_2") (pintype "passive"))
    )
    (net (code "26") (name "/ROW_B1") (class "Default")
      (node (ref "D103") (pin "2") (pinfunction "K_2") (pintype "passive"))
      (node (ref "D111") (pin "2") (pinfunction "K_2") (pintype "passive"))
      (node (ref "D119") (pin "2") (pinfunction "K_2") (pintype "passive"))
      (node (ref "D127") (pin "2") (pinfunction "K_2") (pintype "passive"))
      (node (ref "D15") (pin "2") (pinfunction "K_2") (pintype "passive"))
      (node (ref "D23") (pin "2") (pinfunction "K_2") (pintype "passive"))
      (node (ref "D31") (pin "2") (pinfunction "K_2") (pintype "passive"))
      (node (ref "D39") (pin "2") (pinfunction "K_2") (pintype "passive"))
      (node (ref "D47") (pin "2") (pinfunction "K_2") (pintype "passive"))
      (node (ref "D55") (pin "2") (pinfunction "K_2") (pintype "passive"))
      (node (ref "D63") (pin "2") (pinfunction "K_2") (pintype "passive"))
      (node (ref "D7") (pin "2") (pinfunction "K_2") (pintype "passive"))
      (node (ref "D71") (pin "2") (pinfunction "K_2") (pintype "passive"))
      (node (ref "D79") (pin "2") (pinfunction "K_2") (pintype "passive"))
      (node (ref "D87") (pin "2") (pinfunction "K_2") (pintype "passive"))
      (node (ref "D95") (pin "2") (pinfunction "K_2") (pintype "passive"))
      (node (ref "R10") (pin "2") (pinfunction "2_2") (pintype "passive"))
    )
    (net (code "27") (name "/ROW_B2") (class "Default")
      (node (ref "D102") (pin "2") (pinfunction "K_2") (pintype "passive"))
      (node (ref "D110") (pin "2") (pinfunction "K_2") (pintype "passive"))
      (node (ref "D118") (pin "2") (pinfunction "K_2") (pintype "passive"))
      (node (ref "D126") (pin "2") (pinfunction "K_2") (pintype "passive"))
      (node (ref "D14") (pin "2") (pinfunction "K_2") (pintype "passive"))
      (node (ref "D22") (pin "2") (pinfunction "K_2") (pintype "passive"))
      (node (ref "D30") (pin "2") (pinfunction "K_2") (pintype "passive"))
      (node (ref "D38") (pin "2") (pinfunction "K_2") (pintype "passive"))
      (node (ref "D46") (pin "2") (pinfunction "K_2") (pintype "passive"))
      (node (ref "D54") (pin "2") (pinfunction "K_2") (pintype "passive"))
      (node (ref "D6") (pin "2") (pinfunction "K_2") (pintype "passive"))
      (node (ref "D62") (pin "2") (pinfunction "K_2") (pintype "passive"))
      (node (ref "D70") (pin "2") (pinfunction "K_2") (pintype "passive"))
      (node (ref "D78") (pin "2") (pinfunction "K_2") (pintype "passive"))
      (node (ref "D86") (pin "2") (pinfunction "K_2") (pintype "passive"))
      (node (ref "D94") (pin "2") (pinfunction "K_2") (pintype "passive"))
      (node (ref "R11") (pin "2") (pinfunction "2_2") (pintype "passive"))
    )
    (net (code "28") (name "/ROW_B3") (class "Default")
      (node (ref "D101") (pin "2") (pinfunction "K_2") (pintype "passive"))
      (node (ref "D109") (pin "2") (pinfunction "K_2") (pintype "passive"))
      (node (ref "D117") (pin "2") (pinfunction "K_2") (pintype "passive"))
      (node (ref "D125") (pin "2") (pinfunction "K_2") (pintype "passive"))
      (node (ref "D13") (pin "2") (pinfunction "K_2") (pintype "passive"))
      (node (ref "D21") (pin "2") (pinfunction "K_2") (pintype "passive"))
      (node (ref "D29") (pin "2") (pinfunction "K_2") (pintype "passive"))
      (node (ref "D37") (pin "2") (pinfunction "K_2") (pintype "passive"))
      (node (ref "D45") (pin "2") (pinfunction "K_2") (pintype "passive"))
      (node (ref "D5") (pin "2") (pinfunction "K_2") (pintype "passive"))
      (node (ref "D53") (pin "2") (pinfunction "K_2") (pintype "passive"))
      (node (ref "D61") (pin "2") (pinfunction "K_2") (pintype "passive"))
      (node (ref "D69") (pin "2") (pinfunction "K_2") (pintype "passive"))
      (node (ref "D77") (pin "2") (pinfunction "K_2") (pintype "passive"))
      (node (ref "D85") (pin "2") (pinfunction "K_2") (pintype "passive"))
      (node (ref "D93") (pin "2") (pinfunction "K_2") (pintype "passive"))
      (node (ref "R12") (pin "2") (pinfunction "2_2") (pintype "passive"))
    )
    (net (code "29") (name "/ROW_B4") (class "Default")
      (node (ref "D100") (pin "2") (pinfunction "K_2") (pintype "passive"))
      (node (ref "D108") (pin "2") (pinfunction "K_2") (pintype "passive"))
      (node (ref "D116") (pin "2") (pinfunction "K_2") (pintype "passive"))
      (node (ref "D12") (pin "2") (pinfunction "K_2") (pintype "passive"))
      (node (ref "D124") (pin "2") (pinfunction "K_2") (pintype "passive"))
      (node (ref "D20") (pin "2") (pinfunction "K_2") (pintype "passive"))
      (node (ref "D28") (pin "2") (pinfunction "K_2") (pintype "passive"))
      (node (ref "D36") (pin "2") (pinfunction "K_2") (pintype "passive"))
      (node (ref "D4") (pin "2") (pinfunction "K_2") (pintype "passive"))
      (node (ref "D44") (pin "2") (pinfunction "K_2") (pintype "passive"))
      (node (ref "D52") (pin "2") (pinfunction "K_2") (pintype "passive"))
      (node (ref "D60") (pin "2") (pinfunction "K_2") (pintype "passive"))
      (node (ref "D68") (pin "2") (pinfunction "K_2") (pintype "passive"))
      (node (ref "D76") (pin "2") (pinfunction "K_2") (pintype "passive"))
      (node (ref "D84") (pin "2") (pinfunction "K_2") (pintype "passive"))
      (node (ref "D92") (pin "2") (pinfunction "K_2") (pintype "passive"))
      (node (ref "R13") (pin "2") (pinfunction "2_2") (pintype "passive"))
    )
    (net (code "30") (name "/ROW_B5") (class "Default")
      (node (ref "D107") (pin "2") (pinfunction "K_2") (pintype "passive"))
      (node (ref "D11") (pin "2") (pinfunction "K_2") (pintype "passive"))
      (node (ref "D115") (pin "2") (pinfunction "K_2") (pintype "passive"))
      (node (ref "D123") (pin "2") (pinfunction "K_2") (pintype "passive"))
      (node (ref "D19") (pin "2") (pinfunction "K_2") (pintype "passive"))
      (node (ref "D27") (pin "2") (pinfunction "K_2") (pintype "passive"))
      (node (ref "D3") (pin "2") (pinfunction "K_2") (pintype "passive"))
      (node (ref "D35") (pin "2") (pinfunction "K_2") (pintype "passive"))
      (node (ref "D43") (pin "2") (pinfunction "K_2") (pintype "passive"))
      (node (ref "D51") (pin "2") (pinfunction "K_2") (pintype "passive"))
      (node (ref "D59") (pin "2") (pinfunction "K_2") (pintype "passive"))
      (node (ref "D67") (pin "2") (pinfunction "K_2") (pintype "passive"))
      (node (ref "D75") (pin "2") (pinfunction "K_2") (pintype "passive"))
      (node (ref "D83") (pin "2") (pinfunction "K_2") (pintype "passive"))
      (node (ref "D91") (pin "2") (pinfunction "K_2") (pintype "passive"))
      (node (ref "D99") (pin "2") (pinfunction "K_2") (pintype "passive"))
      (node (ref "R14") (pin "2") (pinfunction "2_2") (pintype "passive"))
    )
    (net (code "31") (name "/ROW_B6") (class "Default")
      (node (ref "D10") (pin "2") (pinfunction "K_2") (pintype "passive"))
      (node (ref "D106") (pin "2") (pinfunction "K_2") (pintype "passive"))
      (node (ref "D114") (pin "2") (pinfunction "K_2") (pintype "passive"))
      (node (ref "D122") (pin "2") (pinfunction "K_2") (pintype "passive"))
      (node (ref "D18") (pin "2") (pinfunction "K_2") (pintype "passive"))
      (node (ref "D2") (pin "2") (pinfunction "K_2") (pintype "passive"))
      (node (ref "D26") (pin "2") (pinfunction "K_2") (pintype "passive"))
      (node (ref "D34") (pin "2") (pinfunction "K_2") (pintype "passive"))
      (node (ref "D42") (pin "2") (pinfunction "K_2") (pintype "passive"))
      (node (ref "D50") (pin "2") (pinfunction "K_2") (pintype "passive"))
      (node (ref "D58") (pin "2") (pinfunction "K_2") (pintype "passive"))
      (node (ref "D66") (pin "2") (pinfunction "K_2") (pintype "passive"))
      (node (ref "D74") (pin "2") (pinfunction "K_2") (pintype "passive"))
      (node (ref "D82") (pin "2") (pinfunction "K_2") (pintype "passive"))
      (node (ref "D90") (pin "2") (pinfunction "K_2") (pintype "passive"))
      (node (ref "D98") (pin "2") (pinfunction "K_2") (pintype "passive"))
      (node (ref "R15") (pin "2") (pinfunction "2_2") (pintype "passive"))
    )
    (net (code "32") (name "/ROW_B7") (class "Default")
      (node (ref "D1") (pin "2") (pinfunction "K_2") (pintype "passive"))
      (node (ref "D105") (pin "2") (pinfunction "K_2") (pintype "passive"))
      (node (ref "D113") (pin "2") (pinfunction "K_2") (pintype "passive"))
      (node (ref "D121") (pin "2") (pinfunction "K_2") (pintype "passive"))
      (node (ref "D17") (pin "2") (pinfunction "K_2") (pintype "passive"))
      (node (ref "D25") (pin "2") (pinfunction "K_2") (pintype "passive"))
      (node (ref "D33") (pin "2") (pinfunction "K_2") (pintype "passive"))
      (node (ref "D41") (pin "2") (pinfunction "K_2") (pintype "passive"))
      (node (ref "D49") (pin "2") (pinfunction "K_2") (pintype "passive"))
      (node (ref "D57") (pin "2") (pinfunction "K_2") (pintype "passive"))
      (node (ref "D65") (pin "2") (pinfunction "K_2") (pintype "passive"))
      (node (ref "D73") (pin "2") (pinfunction "K_2") (pintype "passive"))
      (node (ref "D81") (pin "2") (pinfunction "K_2") (pintype "passive"))
      (node (ref "D89") (pin "2") (pinfunction "K_2") (pintype "passive"))
      (node (ref "D9") (pin "2") (pinfunction "K_2") (pintype "passive"))
      (node (ref "D97") (pin "2") (pinfunction "K_2") (pintype "passive"))
      (node (ref "R16") (pin "2") (pinfunction "2_2") (pintype "passive"))
    )
  )
)
